# LD_v1.net
KiCad netlist of a schematic drawn in EAGLE
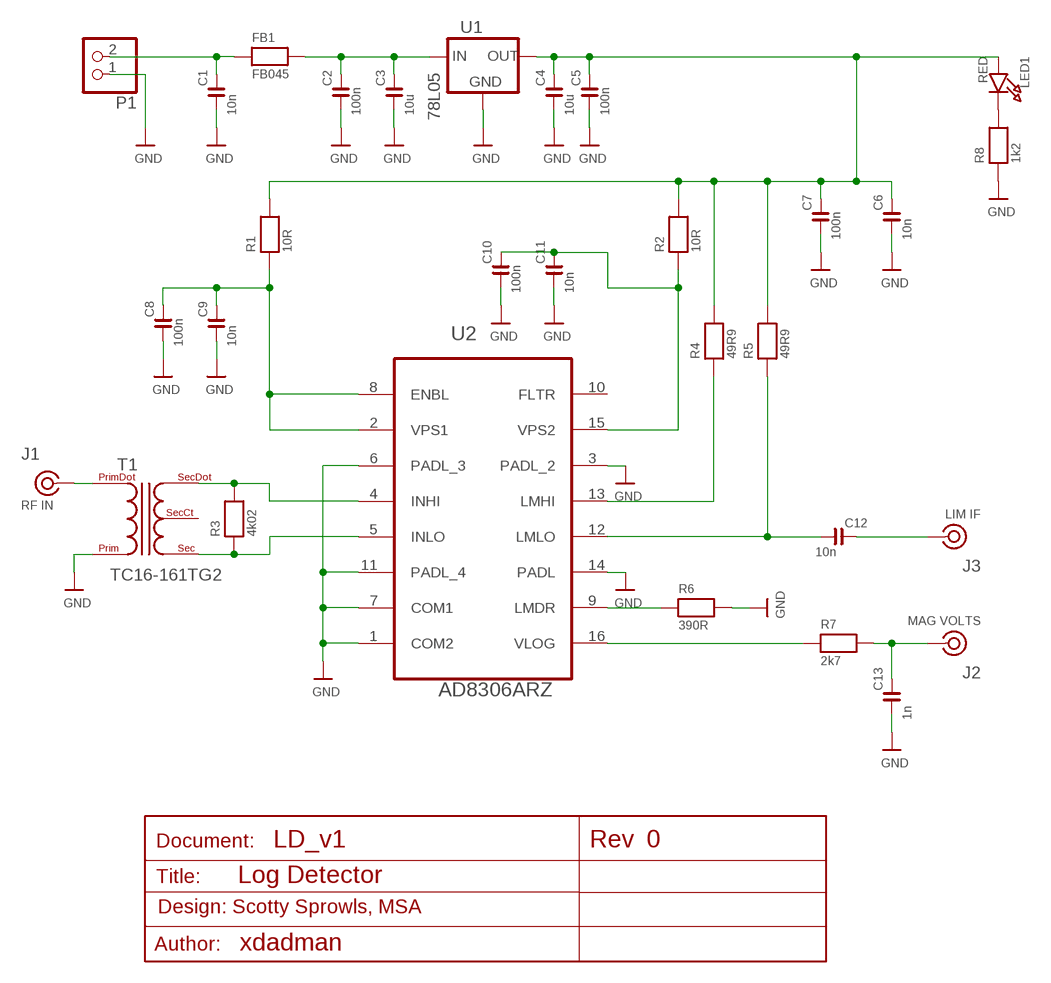
[diagram p0: schematic, sheet 1]

(export (version "E")
  (design (tool "Eeschema 10.0.6"))
  (components
    (comp (ref "C1")
      (value "10n")
      (footprint "eagle-import:C0805")
      (libsource (lib "eagle-import") (part "C080510N"))
    )
    (comp (ref "C2")
      (value "100n")
      (footprint "eagle-import:C0805")
      (libsource (lib "eagle-import") (part "C0805100N"))
    )
    (comp (ref "C3")
      (value "10u")
      (footprint "eagle-import:C1206")
      (libsource (lib "eagle-import") (part "CC120610U"))
    )
    (comp (ref "C4")
      (value "10u")
      (footprint "eagle-import:C1206")
      (libsource (lib "eagle-import") (part "CC120610U"))
    )
    (comp (ref "C5")
      (value "100n")
      (footprint "eagle-import:C0805")
      (libsource (lib "eagle-import") (part "C0805100N"))
    )
    (comp (ref "C6")
      (value "10n")
      (footprint "eagle-import:C0805")
      (libsource (lib "eagle-import") (part "C080510N"))
    )
    (comp (ref "C7")
      (value "100n")
      (footprint "eagle-import:C0805")
      (libsource (lib "eagle-import") (part "C0805100N"))
    )
    (comp (ref "C8")
      (value "100n")
      (footprint "eagle-import:C0805")
      (libsource (lib "eagle-import") (part "C0805100N"))
    )
    (comp (ref "C9")
      (value "10n")
      (footprint "eagle-import:C0805")
      (libsource (lib "eagle-import") (part "C080510N"))
    )
    (comp (ref "C10")
      (value "100n")
      (footprint "eagle-import:C0805")
      (libsource (lib "eagle-import") (part "C0805100N"))
    )
    (comp (ref "C11")
      (value "10n")
      (footprint "eagle-import:C0805")
      (libsource (lib "eagle-import") (part "C080510N"))
    )
    (comp (ref "C12")
      (value "10n")
      (footprint "eagle-import:C0805")
      (libsource (lib "eagle-import") (part "C080510N"))
    )
    (comp (ref "C13")
      (value "1n")
      (footprint "eagle-import:C0805")
      (libsource (lib "eagle-import") (part "C08051N"))
    )
    (comp (ref "FB1")
      (value "FB045")
      (footprint "eagle-import:R0805")
      (libsource (lib "eagle-import") (part "R0805FB045"))
    )
    (comp (ref "J1")
      (value "RF IN")
      (footprint "eagle-import:SLIM_COAX_PAD")
      (libsource (lib "eagle-import") (part "COAX"))
    )
    (comp (ref "J2")
      (value "MAG VOLTS")
      (footprint "eagle-import:SLIM_COAX_PAD")
      (libsource (lib "eagle-import") (part "COAX"))
    )
    (comp (ref "J3")
      (value "LIM IF")
      (footprint "eagle-import:SLIM_COAX_PAD")
      (libsource (lib "eagle-import") (part "COAX"))
    )
    (comp (ref "LED1")
      (value "RED")
      (footprint "eagle-import:CHIPLED_0603")
      (libsource (lib "eagle-import") (part "LED_0603_RED0603"))
    )
    (comp (ref "P1")
      (value "PINHD-1X2")
      (footprint "eagle-import:1X02")
      (libsource (lib "eagle-import") (part "PINHD-1X2"))
    )
    (comp (ref "R1")
      (value "10R")
      (footprint "eagle-import:R0805")
      (libsource (lib "eagle-import") (part "R080510R"))
    )
    (comp (ref "R2")
      (value "10R")
      (footprint "eagle-import:R0805")
      (libsource (lib "eagle-import") (part "R080510R"))
    )
    (comp (ref "R3")
      (value "4k02")
      (footprint "eagle-import:R0805")
      (libsource (lib "eagle-import") (part "R08054K02"))
    )
    (comp (ref "R4")
      (value "49R9")
      (footprint "eagle-import:R0805")
      (libsource (lib "eagle-import") (part "R080549R9"))
    )
    (comp (ref "R5")
      (value "49R9")
      (footprint "eagle-import:R0805")
      (libsource (lib "eagle-import") (part "R080549R9"))
    )
    (comp (ref "R6")
      (value "390R")
      (footprint "eagle-import:R0805")
      (libsource (lib "eagle-import") (part "R0805390R"))
    )
    (comp (ref "R7")
      (value "2k7")
      (footprint "eagle-import:R0805")
      (libsource (lib "eagle-import") (part "R08052K7"))
    )
    (comp (ref "R8")
      (value "1k2")
      (footprint "eagle-import:R0805")
      (libsource (lib "eagle-import") (part "R08051K2"))
    )
    (comp (ref "T1")
      (value "TC16-161TG2")
      (footprint "eagle-import:TC16-161TG2")
      (libsource (lib "eagle-import") (part "TC16-161TG2"))
    )
    (comp (ref "U1")
      (value "78L05")
      (footprint "eagle-import:SOT89")
      (libsource (lib "eagle-import") (part "78MXXL78L05"))
    )
    (comp (ref "U2")
      (value "AD8306ARZ")
      (footprint "eagle-import:SOIC16")
      (libsource (lib "eagle-import") (part "AD8306ARZ"))
    )
  )
  (nets
    (net (code "1") (name "GND") (class "Default")
      (node (ref "C1") (pin "1") (pinfunction "1_1") (pintype "passive"))
      (node (ref "C10") (pin "1") (pinfunction "1_1") (pintype "passive"))
      (node (ref "C11") (pin "1") (pinfunction "1_1") (pintype "passive"))
      (node (ref "C13") (pin "1") (pinfunction "1_1") (pintype "passive"))
      (node (ref "C2") (pin "1") (pinfunction "1_1") (pintype "passive"))
      (node (ref "C3") (pin "1") (pinfunction "1_1") (pintype "passive"))
      (node (ref "C4") (pin "1") (pinfunction "1_1") (pintype "passive"))
      (node (ref "C5") (pin "1") (pinfunction "1_1") (pintype "passive"))
      (node (ref "C6") (pin "1") (pinfunction "1_1") (pintype "passive"))
      (node (ref "C7") (pin "1") (pinfunction "1_1") (pintype "passive"))
      (node (ref "C8") (pin "1") (pinfunction "1_1") (pintype "passive"))
      (node (ref "C9") (pin "1") (pinfunction "1_1") (pintype "passive"))
      (node (ref "P1") (pin "1") (pinfunction "1_1") (pintype "passive"))
      (node (ref "R6") (pin "2") (pinfunction "2_2") (pintype "passive"))
      (node (ref "R8") (pin "1") (pinfunction "1_1") (pintype "passive"))
      (node (ref "T1") (pin "4") (pinfunction "4_4") (pintype "passive"))
      (node (ref "U1") (pin "2") (pinfunction "GND_2") (pintype "input"))
      (node (ref "U1") (pin "4") (pinfunction "GND_4") (pintype "input"))
      (node (ref "U2") (pin "1") (pinfunction "COM2_1") (pintype "passive"))
      (node (ref "U2") (pin "11") (pinfunction "PADL_4_11") (pintype "passive"))
      (node (ref "U2") (pin "14") (pinfunction "PADL_14") (pintype "passive"))
      (node (ref "U2") (pin "3") (pinfunction "PADL_2_3") (pintype "passive"))
      (node (ref "U2") (pin "6") (pinfunction "PADL_3_6") (pintype "passive"))
      (node (ref "U2") (pin "7") (pinfunction "COM1_7") (pintype "passive"))
    )
    (net (code "2") (name "Net-(C1-Pad2)") (class "Default")
      (node (ref "C1") (pin "2") (pinfunction "2_2") (pintype "passive"))
      (node (ref "FB1") (pin "1") (pinfunction "1_1") (pintype "passive"))
      (node (ref "P1") (pin "2") (pinfunction "2_2") (pintype "passive"))
    )
    (net (code "3") (name "Net-(J1A-1)") (class "Default")
      (node (ref "J1") (pin "SIG") (pinfunction "1_SIG") (pintype "passive"))
      (node (ref "T1") (pin "6") (pinfunction "6_6") (pintype "passive"))
    )
    (net (code "4") (name "Net-(J2A-1)") (class "Default")
      (node (ref "C13") (pin "2") (pinfunction "2_2") (pintype "passive"))
      (node (ref "J2") (pin "SIG") (pinfunction "1_SIG") (pintype "passive"))
      (node (ref "R7") (pin "2") (pinfunction "2_2") (pintype "passive"))
    )
    (net (code "5") (name "Net-(J3A-1)") (class "Default")
      (node (ref "C12") (pin "2") (pinfunction "2_2") (pintype "passive"))
      (node (ref "J3") (pin "SIG") (pinfunction "1_SIG") (pintype "passive"))
    )
    (net (code "6") (name "Net-(LED1-PadC)") (class "Default")
      (node (ref "LED1") (pin "C") (pinfunction "C_C") (pintype "passive"))
      (node (ref "R8") (pin "2") (pinfunction "2_2") (pintype "passive"))
    )
    (net (code "7") (name "Net-(U1-IN)") (class "Default")
      (node (ref "C2") (pin "2") (pinfunction "2_2") (pintype "passive"))
      (node (ref "C3") (pin "2") (pinfunction "2_2") (pintype "passive"))
      (node (ref "FB1") (pin "2") (pinfunction "2_2") (pintype "passive"))
      (node (ref "U1") (pin "3") (pinfunction "IN_3") (pintype "input"))
    )
    (net (code "8") (name "Net-(U1-OUT)") (class "Default")
      (node (ref "C4") (pin "2") (pinfunction "2_2") (pintype "passive"))
      (node (ref "C5") (pin "2") (pinfunction "2_2") (pintype "passive"))
      (node (ref "C6") (pin "2") (pinfunction "2_2") (pintype "passive"))
      (node (ref "C7") (pin "2") (pinfunction "2_2") (pintype "passive"))
      (node (ref "LED1") (pin "A") (pinfunction "A_A") (pintype "passive"))
      (node (ref "R1") (pin "2") (pinfunction "2_2") (pintype "passive"))
      (node (ref "R2") (pin "2") (pinfunction "2_2") (pintype "passive"))
      (node (ref "R4") (pin "2") (pinfunction "2_2") (pintype "passive"))
      (node (ref "R5") (pin "2") (pinfunction "2_2") (pintype "passive"))
      (node (ref "U1") (pin "1") (pinfunction "OUT_1") (pintype "passive"))
    )
    (net (code "9") (name "Net-(U2-ENBL)") (class "Default")
      (node (ref "C8") (pin "2") (pinfunction "2_2") (pintype "passive"))
      (node (ref "C9") (pin "2") (pinfunction "2_2") (pintype "passive"))
      (node (ref "R1") (pin "1") (pinfunction "1_1") (pintype "passive"))
      (node (ref "U2") (pin "2") (pinfunction "VPS1_2") (pintype "power_in"))
      (node (ref "U2") (pin "8") (pinfunction "ENBL_8") (pintype "input"))
    )
    (net (code "10") (name "Net-(U2-INHI)") (class "Default")
      (node (ref "R3") (pin "2") (pinfunction "2_2") (pintype "passive"))
      (node (ref "T1") (pin "1") (pinfunction "1_1") (pintype "passive"))
      (node (ref "U2") (pin "4") (pinfunction "INHI_4") (pintype "input"))
    )
    (net (code "11") (name "Net-(U2-INLO)") (class "Default")
      (node (ref "R3") (pin "1") (pinfunction "1_1") (pintype "passive"))
      (node (ref "T1") (pin "3") (pinfunction "3_3") (pintype "passive"))
      (node (ref "U2") (pin "5") (pinfunction "INLO_5") (pintype "input"))
    )
    (net (code "12") (name "Net-(U2-LMDR)") (class "Default")
      (node (ref "R6") (pin "1") (pinfunction "1_1") (pintype "passive"))
      (node (ref "U2") (pin "9") (pinfunction "LMDR_9") (pintype "passive"))
    )
    (net (code "13") (name "Net-(U2-LMHI)") (class "Default")
      (node (ref "R4") (pin "1") (pinfunction "1_1") (pintype "passive"))
      (node (ref "U2") (pin "13") (pinfunction "LMHI_13") (pintype "output"))
    )
    (net (code "14") (name "Net-(U2-LMLO)") (class "Default")
      (node (ref "C12") (pin "1") (pinfunction "1_1") (pintype "passive"))
      (node (ref "R5") (pin "1") (pinfunction "1_1") (pintype "passive"))
      (node (ref "U2") (pin "12") (pinfunction "LMLO_12") (pintype "output"))
    )
    (net (code "15") (name "Net-(U2-VLOG)") (class "Default")
      (node (ref "R7") (pin "1") (pinfunction "1_1") (pintype "passive"))
      (node (ref "U2") (pin "16") (pinfunction "VLOG_16") (pintype "output"))
    )
    (net (code "16") (name "Net-(U2-VPS2)") (class "Default")
      (node (ref "C10") (pin "2") (pinfunction "2_2") (pintype "passive"))
      (node (ref "C11") (pin "2") (pinfunction "2_2") (pintype "passive"))
      (node (ref "R2") (pin "1") (pinfunction "1_1") (pintype "passive"))
      (node (ref "U2") (pin "15") (pinfunction "VPS2_15") (pintype "power_in"))
    )
    (net (code "17") (name "unconnected-(T1-Pad2)") (class "Default")
      (node (ref "T1") (pin "2") (pinfunction "2_2") (pintype "passive"))
    )
    (net (code "18") (name "unconnected-(U2-FLTR-Pad10)") (class "Default")
      (node (ref "U2") (pin "10") (pinfunction "FLTR_10") (pintype "passive"))
    )
  )
)
